# cooling_system_at8pu.net
KiCad netlist of a schematic drawn in EAGLE
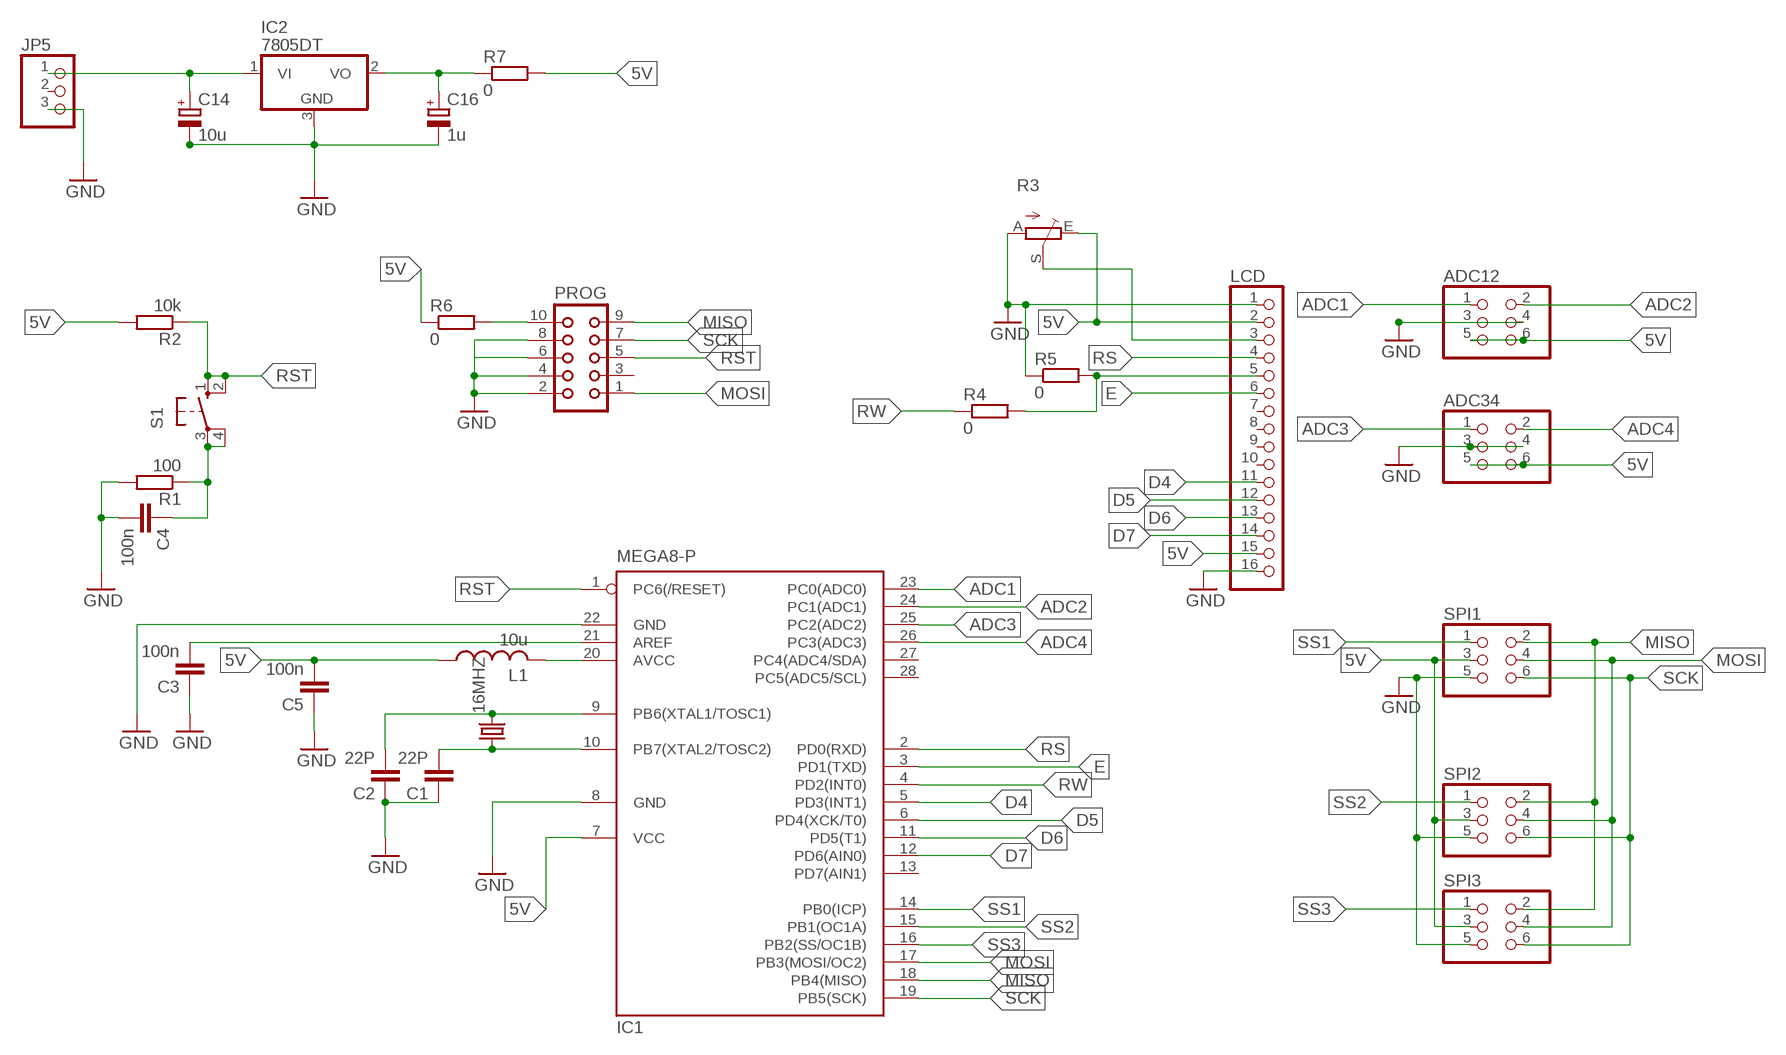
[diagram p0: schematic, sheet 1]

(export (version "E")
  (design (tool "Eeschema 10.0.6"))
  (components
    (comp (ref "16MHZ")
      (value "CRYSTALHC18U-V")
      (footprint "eagle-import:HC18U-V")
      (libsource (lib "eagle-import") (part "CRYSTALHC18U-V"))
    )
    (comp (ref "ADC12")
      (value "PINHD-2X3")
      (footprint "eagle-import:2X03")
      (libsource (lib "eagle-import") (part "PINHD-2X3"))
    )
    (comp (ref "ADC34")
      (value "PINHD-2X3")
      (footprint "eagle-import:2X03")
      (libsource (lib "eagle-import") (part "PINHD-2X3"))
    )
    (comp (ref "C1")
      (value "22P")
      (footprint "eagle-import:C0805")
      (libsource (lib "eagle-import") (part "C-EUC0805"))
    )
    (comp (ref "C2")
      (value "22P")
      (footprint "eagle-import:C0805")
      (libsource (lib "eagle-import") (part "C-EUC0805"))
    )
    (comp (ref "C3")
      (value "100n")
      (footprint "eagle-import:C0805")
      (libsource (lib "eagle-import") (part "C-EUC0805"))
    )
    (comp (ref "C4")
      (value "100n")
      (footprint "eagle-import:C0805")
      (libsource (lib "eagle-import") (part "C-EUC0805"))
    )
    (comp (ref "C5")
      (value "100n")
      (footprint "eagle-import:C0805")
      (libsource (lib "eagle-import") (part "C-EUC0805"))
    )
    (comp (ref "C14")
      (value "10u")
      (footprint "eagle-import:153CLV-0605")
      (libsource (lib "eagle-import") (part "CPOL-EU153CLV-0605"))
    )
    (comp (ref "C16")
      (value "1u")
      (footprint "eagle-import:153CLV-0405")
      (libsource (lib "eagle-import") (part "CPOL-EU153CLV-0405"))
    )
    (comp (ref "IC1")
      (value "MEGA8-P")
      (footprint "eagle-import:DIL28-3")
      (libsource (lib "eagle-import") (part "MEGA8-P"))
    )
    (comp (ref "IC2")
      (value "7805DT")
      (footprint "eagle-import:TO252")
      (libsource (lib "eagle-import") (part "78DT05"))
    )
    (comp (ref "JP5")
      (value "PINHD-1X3")
      (footprint "eagle-import:1X03")
      (libsource (lib "eagle-import") (part "PINHD-1X3"))
    )
    (comp (ref "L1")
      (value "10u")
      (footprint "eagle-import:0204_7")
      (libsource (lib "eagle-import") (part "L-US0204/7"))
    )
    (comp (ref "LCD")
      (value "PINHD-1X16")
      (footprint "eagle-import:1X16")
      (libsource (lib "eagle-import") (part "PINHD-1X16"))
    )
    (comp (ref "PROG")
      (value "CON10")
      (footprint "eagle-import:CON10")
      (libsource (lib "eagle-import") (part "CON10"))
    )
    (comp (ref "R1")
      (value "100")
      (footprint "eagle-import:0207_10")
      (libsource (lib "eagle-import") (part "R-EU_0207/10"))
    )
    (comp (ref "R2")
      (value "10k")
      (footprint "eagle-import:0207_10")
      (libsource (lib "eagle-import") (part "R-EU_0207/10"))
    )
    (comp (ref "R3")
      (value "TRIM_EU-CT6")
      (footprint "eagle-import:CT6")
      (libsource (lib "eagle-import") (part "TRIM_EU-CT6"))
    )
    (comp (ref "R4")
      (value "0")
      (footprint "eagle-import:R0805")
      (libsource (lib "eagle-import") (part "R-EU_R0805"))
    )
    (comp (ref "R5")
      (value "0")
      (footprint "eagle-import:R0805")
      (libsource (lib "eagle-import") (part "R-EU_R0805"))
    )
    (comp (ref "R6")
      (value "0")
      (footprint "eagle-import:R0805")
      (libsource (lib "eagle-import") (part "R-EU_R0805"))
    )
    (comp (ref "R7")
      (value "0")
      (footprint "eagle-import:R0805")
      (libsource (lib "eagle-import") (part "R-EU_R0805"))
    )
    (comp (ref "S1")
      (value "10-XX")
      (footprint "eagle-import:B3F-10XX")
      (fields (field (name "MPN") "B3F-1000"))
      (libsource (lib "eagle-import") (part "10-XX"))
    )
    (comp (ref "SPI1")
      (value "PINHD-2X3")
      (footprint "eagle-import:2X03")
      (libsource (lib "eagle-import") (part "PINHD-2X3"))
    )
    (comp (ref "SPI2")
      (value "PINHD-2X3")
      (footprint "eagle-import:2X03")
      (libsource (lib "eagle-import") (part "PINHD-2X3"))
    )
    (comp (ref "SPI3")
      (value "PINHD-2X3")
      (footprint "eagle-import:2X03")
      (libsource (lib "eagle-import") (part "PINHD-2X3"))
    )
  )
  (nets
    (net (code "1") (name "5V") (class "Default")
      (node (ref "ADC12") (pin "5") (pinfunction "5_5") (pintype "passive"))
      (node (ref "ADC12") (pin "6") (pinfunction "6_6") (pintype "passive"))
      (node (ref "ADC34") (pin "5") (pinfunction "5_5") (pintype "passive"))
      (node (ref "ADC34") (pin "6") (pinfunction "6_6") (pintype "passive"))
      (node (ref "C5") (pin "2") (pinfunction "2_2") (pintype "passive"))
      (node (ref "IC1") (pin "7") (pinfunction "VCC_7") (pintype "power_in"))
      (node (ref "L1") (pin "1") (pinfunction "1_1") (pintype "passive"))
      (node (ref "LCD") (pin "15") (pinfunction "15_15") (pintype "passive"))
      (node (ref "LCD") (pin "2") (pinfunction "2_2") (pintype "passive"))
      (node (ref "R2") (pin "2") (pinfunction "2_2") (pintype "passive"))
      (node (ref "R3") (pin "E") (pinfunction "E_E") (pintype "passive"))
      (node (ref "R6") (pin "1") (pinfunction "1_1") (pintype "passive"))
      (node (ref "R7") (pin "2") (pinfunction "2_2") (pintype "passive"))
      (node (ref "SPI1") (pin "3") (pinfunction "3_3") (pintype "passive"))
      (node (ref "SPI2") (pin "3") (pinfunction "3_3") (pintype "passive"))
      (node (ref "SPI3") (pin "3") (pinfunction "3_3") (pintype "passive"))
    )
    (net (code "2") (name "ADC1") (class "Default")
      (node (ref "ADC12") (pin "1") (pinfunction "1_1") (pintype "passive"))
      (node (ref "IC1") (pin "23") (pinfunction "PC0(ADC0)_23") (pintype "bidirectional"))
    )
    (net (code "3") (name "ADC2") (class "Default")
      (node (ref "ADC12") (pin "2") (pinfunction "2_2") (pintype "passive"))
      (node (ref "IC1") (pin "24") (pinfunction "PC1(ADC1)_24") (pintype "bidirectional"))
    )
    (net (code "4") (name "ADC3") (class "Default")
      (node (ref "ADC34") (pin "1") (pinfunction "1_1") (pintype "passive"))
      (node (ref "IC1") (pin "25") (pinfunction "PC2(ADC2)_25") (pintype "bidirectional"))
    )
    (net (code "5") (name "ADC4") (class "Default")
      (node (ref "ADC34") (pin "2") (pinfunction "2_2") (pintype "passive"))
      (node (ref "IC1") (pin "26") (pinfunction "PC3(ADC3)_26") (pintype "bidirectional"))
    )
    (net (code "6") (name "D4") (class "Default")
      (node (ref "IC1") (pin "5") (pinfunction "PD3(INT1)_5") (pintype "bidirectional"))
      (node (ref "LCD") (pin "11") (pinfunction "11_11") (pintype "passive"))
    )
    (net (code "7") (name "D5") (class "Default")
      (node (ref "IC1") (pin "6") (pinfunction "PD4(XCK/T0)_6") (pintype "bidirectional"))
      (node (ref "LCD") (pin "12") (pinfunction "12_12") (pintype "passive"))
    )
    (net (code "8") (name "D6") (class "Default")
      (node (ref "IC1") (pin "11") (pinfunction "PD5(T1)_11") (pintype "bidirectional"))
      (node (ref "LCD") (pin "13") (pinfunction "13_13") (pintype "passive"))
    )
    (net (code "9") (name "D7") (class "Default")
      (node (ref "IC1") (pin "12") (pinfunction "PD6(AIN0)_12") (pintype "bidirectional"))
      (node (ref "LCD") (pin "14") (pinfunction "14_14") (pintype "passive"))
    )
    (net (code "10") (name "E") (class "Default")
      (node (ref "IC1") (pin "3") (pinfunction "PD1(TXD)_3") (pintype "bidirectional"))
      (node (ref "LCD") (pin "6") (pinfunction "6_6") (pintype "passive"))
    )
    (net (code "11") (name "GND") (class "Default")
      (node (ref "ADC12") (pin "3") (pinfunction "3_3") (pintype "passive"))
      (node (ref "ADC12") (pin "4") (pinfunction "4_4") (pintype "passive"))
      (node (ref "ADC34") (pin "3") (pinfunction "3_3") (pintype "passive"))
      (node (ref "ADC34") (pin "4") (pinfunction "4_4") (pintype "passive"))
      (node (ref "C1") (pin "1") (pinfunction "1_1") (pintype "passive"))
      (node (ref "C14") (pin "-") (pinfunction "-_-") (pintype "passive"))
      (node (ref "C16") (pin "-") (pinfunction "-_-") (pintype "passive"))
      (node (ref "C2") (pin "1") (pinfunction "1_1") (pintype "passive"))
      (node (ref "C3") (pin "1") (pinfunction "1_1") (pintype "passive"))
      (node (ref "C4") (pin "2") (pinfunction "2_2") (pintype "passive"))
      (node (ref "C5") (pin "1") (pinfunction "1_1") (pintype "passive"))
      (node (ref "IC1") (pin "22") (pinfunction "GND_22") (pintype "power_in"))
      (node (ref "IC1") (pin "8") (pinfunction "GND_8") (pintype "power_in"))
      (node (ref "IC2") (pin "3") (pinfunction "GND_3") (pintype "passive"))
      (node (ref "JP5") (pin "3") (pinfunction "3_3") (pintype "passive"))
      (node (ref "LCD") (pin "1") (pinfunction "1_1") (pintype "passive"))
      (node (ref "LCD") (pin "16") (pinfunction "16_16") (pintype "passive"))
      (node (ref "PROG") (pin "2") (pinfunction "2_2") (pintype "passive"))
      (node (ref "PROG") (pin "4") (pinfunction "4_4") (pintype "passive"))
      (node (ref "PROG") (pin "6") (pinfunction "6_6") (pintype "passive"))
      (node (ref "PROG") (pin "8") (pinfunction "8_8") (pintype "passive"))
      (node (ref "R1") (pin "2") (pinfunction "2_2") (pintype "passive"))
      (node (ref "R3") (pin "A") (pinfunction "A_A") (pintype "passive"))
      (node (ref "R5") (pin "1") (pinfunction "1_1") (pintype "passive"))
      (node (ref "SPI1") (pin "5") (pinfunction "5_5") (pintype "passive"))
      (node (ref "SPI2") (pin "5") (pinfunction "5_5") (pintype "passive"))
      (node (ref "SPI3") (pin "5") (pinfunction "5_5") (pintype "passive"))
    )
    (net (code "12") (name "MISO") (class "Default")
      (node (ref "IC1") (pin "18") (pinfunction "PB4(MISO)_18") (pintype "bidirectional"))
      (node (ref "PROG") (pin "9") (pinfunction "9_9") (pintype "passive"))
      (node (ref "SPI1") (pin "2") (pinfunction "2_2") (pintype "passive"))
      (node (ref "SPI2") (pin "2") (pinfunction "2_2") (pintype "passive"))
      (node (ref "SPI3") (pin "2") (pinfunction "2_2") (pintype "passive"))
    )
    (net (code "13") (name "MOSI") (class "Default")
      (node (ref "IC1") (pin "17") (pinfunction "PB3(MOSI/OC2)_17") (pintype "bidirectional"))
      (node (ref "PROG") (pin "1") (pinfunction "1_1") (pintype "passive"))
      (node (ref "SPI1") (pin "4") (pinfunction "4_4") (pintype "passive"))
      (node (ref "SPI2") (pin "4") (pinfunction "4_4") (pintype "passive"))
      (node (ref "SPI3") (pin "4") (pinfunction "4_4") (pintype "passive"))
    )
    (net (code "14") (name "Net-(IC1-AREF)") (class "Default")
      (node (ref "C3") (pin "2") (pinfunction "2_2") (pintype "passive"))
      (node (ref "IC1") (pin "21") (pinfunction "AREF_21") (pintype "passive"))
    )
    (net (code "15") (name "Net-(IC1-AVCC)") (class "Default")
      (node (ref "IC1") (pin "20") (pinfunction "AVCC_20") (pintype "power_in"))
      (node (ref "L1") (pin "2") (pinfunction "2_2") (pintype "passive"))
    )
    (net (code "16") (name "Net-(IC1-PB6(XTAL1{slash}TOSC1))") (class "Default")
      (node (ref "16MHZ") (pin "2") (pinfunction "2_2") (pintype "passive"))
      (node (ref "C2") (pin "2") (pinfunction "2_2") (pintype "passive"))
      (node (ref "IC1") (pin "9") (pinfunction "PB6(XTAL1/TOSC1)_9") (pintype "bidirectional"))
    )
    (net (code "17") (name "Net-(IC1-PB7(XTAL2{slash}TOSC2))") (class "Default")
      (node (ref "16MHZ") (pin "1") (pinfunction "1_1") (pintype "passive"))
      (node (ref "C1") (pin "2") (pinfunction "2_2") (pintype "passive"))
      (node (ref "IC1") (pin "10") (pinfunction "PB7(XTAL2/TOSC2)_10") (pintype "bidirectional"))
    )
    (net (code "18") (name "Net-(IC2-VI)") (class "Default")
      (node (ref "C14") (pin "+") (pinfunction "+_+") (pintype "passive"))
      (node (ref "IC2") (pin "1") (pinfunction "VI_1") (pintype "input"))
      (node (ref "JP5") (pin "1") (pinfunction "1_1") (pintype "passive"))
    )
    (net (code "19") (name "Net-(IC2-VO)") (class "Default")
      (node (ref "C16") (pin "+") (pinfunction "+_+") (pintype "passive"))
      (node (ref "IC2") (pin "2") (pinfunction "VO_2") (pintype "passive"))
      (node (ref "R7") (pin "1") (pinfunction "1_1") (pintype "passive"))
    )
    (net (code "20") (name "Net-(LCD-Pad3)") (class "Default")
      (node (ref "LCD") (pin "3") (pinfunction "3_3") (pintype "passive"))
      (node (ref "R3") (pin "S") (pinfunction "S_S") (pintype "passive"))
    )
    (net (code "21") (name "Net-(LCD-Pad5)") (class "Default")
      (node (ref "LCD") (pin "5") (pinfunction "5_5") (pintype "passive"))
      (node (ref "R4") (pin "2") (pinfunction "2_2") (pintype "passive"))
      (node (ref "R5") (pin "2") (pinfunction "2_2") (pintype "passive"))
    )
    (net (code "22") (name "Net-(PROG-Pad10)") (class "Default")
      (node (ref "PROG") (pin "10") (pinfunction "10_10") (pintype "passive"))
      (node (ref "R6") (pin "2") (pinfunction "2_2") (pintype "passive"))
    )
    (net (code "23") (name "Net-(S1-P)") (class "Default")
      (node (ref "C4") (pin "1") (pinfunction "1_1") (pintype "passive"))
      (node (ref "R1") (pin "1") (pinfunction "1_1") (pintype "passive"))
      (node (ref "S1") (pin "3") (pinfunction "P_3") (pintype "passive"))
      (node (ref "S1") (pin "4") (pinfunction "P1_4") (pintype "passive"))
    )
    (net (code "24") (name "RS") (class "Default")
      (node (ref "IC1") (pin "2") (pinfunction "PD0(RXD)_2") (pintype "bidirectional"))
      (node (ref "LCD") (pin "4") (pinfunction "4_4") (pintype "passive"))
    )
    (net (code "25") (name "RST") (class "Default")
      (node (ref "IC1") (pin "1") (pinfunction "PC6(/RESET)_1") (pintype "bidirectional"))
      (node (ref "PROG") (pin "5") (pinfunction "5_5") (pintype "passive"))
      (node (ref "R2") (pin "1") (pinfunction "1_1") (pintype "passive"))
      (node (ref "S1") (pin "1") (pinfunction "S_1") (pintype "passive"))
      (node (ref "S1") (pin "2") (pinfunction "S1_2") (pintype "passive"))
    )
    (net (code "26") (name "RW") (class "Default")
      (node (ref "IC1") (pin "4") (pinfunction "PD2(INT0)_4") (pintype "bidirectional"))
      (node (ref "R4") (pin "1") (pinfunction "1_1") (pintype "passive"))
    )
    (net (code "27") (name "SCK") (class "Default")
      (node (ref "IC1") (pin "19") (pinfunction "PB5(SCK)_19") (pintype "bidirectional"))
      (node (ref "PROG") (pin "7") (pinfunction "7_7") (pintype "passive"))
      (node (ref "SPI1") (pin "6") (pinfunction "6_6") (pintype "passive"))
      (node (ref "SPI2") (pin "6") (pinfunction "6_6") (pintype "passive"))
      (node (ref "SPI3") (pin "6") (pinfunction "6_6") (pintype "passive"))
    )
    (net (code "28") (name "SS1") (class "Default")
      (node (ref "IC1") (pin "14") (pinfunction "PB0(ICP)_14") (pintype "bidirectional"))
      (node (ref "SPI1") (pin "1") (pinfunction "1_1") (pintype "passive"))
    )
    (net (code "29") (name "SS2") (class "Default")
      (node (ref "IC1") (pin "15") (pinfunction "PB1(OC1A)_15") (pintype "bidirectional"))
      (node (ref "SPI2") (pin "1") (pinfunction "1_1") (pintype "passive"))
    )
    (net (code "30") (name "SS3") (class "Default")
      (node (ref "IC1") (pin "16") (pinfunction "PB2(SS/OC1B)_16") (pintype "bidirectional"))
      (node (ref "SPI3") (pin "1") (pinfunction "1_1") (pintype "passive"))
    )
    (net (code "31") (name "unconnected-(IC1-PC4(ADC4{slash}SDA)-Pad27)") (class "Default")
      (node (ref "IC1") (pin "27") (pinfunction "PC4(ADC4/SDA)_27") (pintype "bidirectional"))
    )
    (net (code "32") (name "unconnected-(IC1-PC5(ADC5{slash}SCL)-Pad28)") (class "Default")
      (node (ref "IC1") (pin "28") (pinfunction "PC5(ADC5/SCL)_28") (pintype "bidirectional"))
    )
    (net (code "33") (name "unconnected-(IC1-PD7(AIN1)-Pad13)") (class "Default")
      (node (ref "IC1") (pin "13") (pinfunction "PD7(AIN1)_13") (pintype "bidirectional"))
    )
    (net (code "34") (name "unconnected-(JP5-Pad2)") (class "Default")
      (node (ref "JP5") (pin "2") (pinfunction "2_2") (pintype "passive"))
    )
    (net (code "35") (name "unconnected-(LCD-Pad7)") (class "Default")
      (node (ref "LCD") (pin "7") (pinfunction "7_7") (pintype "passive"))
    )
    (net (code "36") (name "unconnected-(LCD-Pad8)") (class "Default")
      (node (ref "LCD") (pin "8") (pinfunction "8_8") (pintype "passive"))
    )
    (net (code "37") (name "unconnected-(LCD-Pad9)") (class "Default")
      (node (ref "LCD") (pin "9") (pinfunction "9_9") (pintype "passive"))
    )
    (net (code "38") (name "unconnected-(LCD-Pad10)") (class "Default")
      (node (ref "LCD") (pin "10") (pinfunction "10_10") (pintype "passive"))
    )
    (net (code "39") (name "unconnected-(PROG-Pad3)") (class "Default")
      (node (ref "PROG") (pin "3") (pinfunction "3_3") (pintype "passive"))
    )
  )
)
